# Cathode.net
KiCad netlist of a schematic drawn in Altium Designer
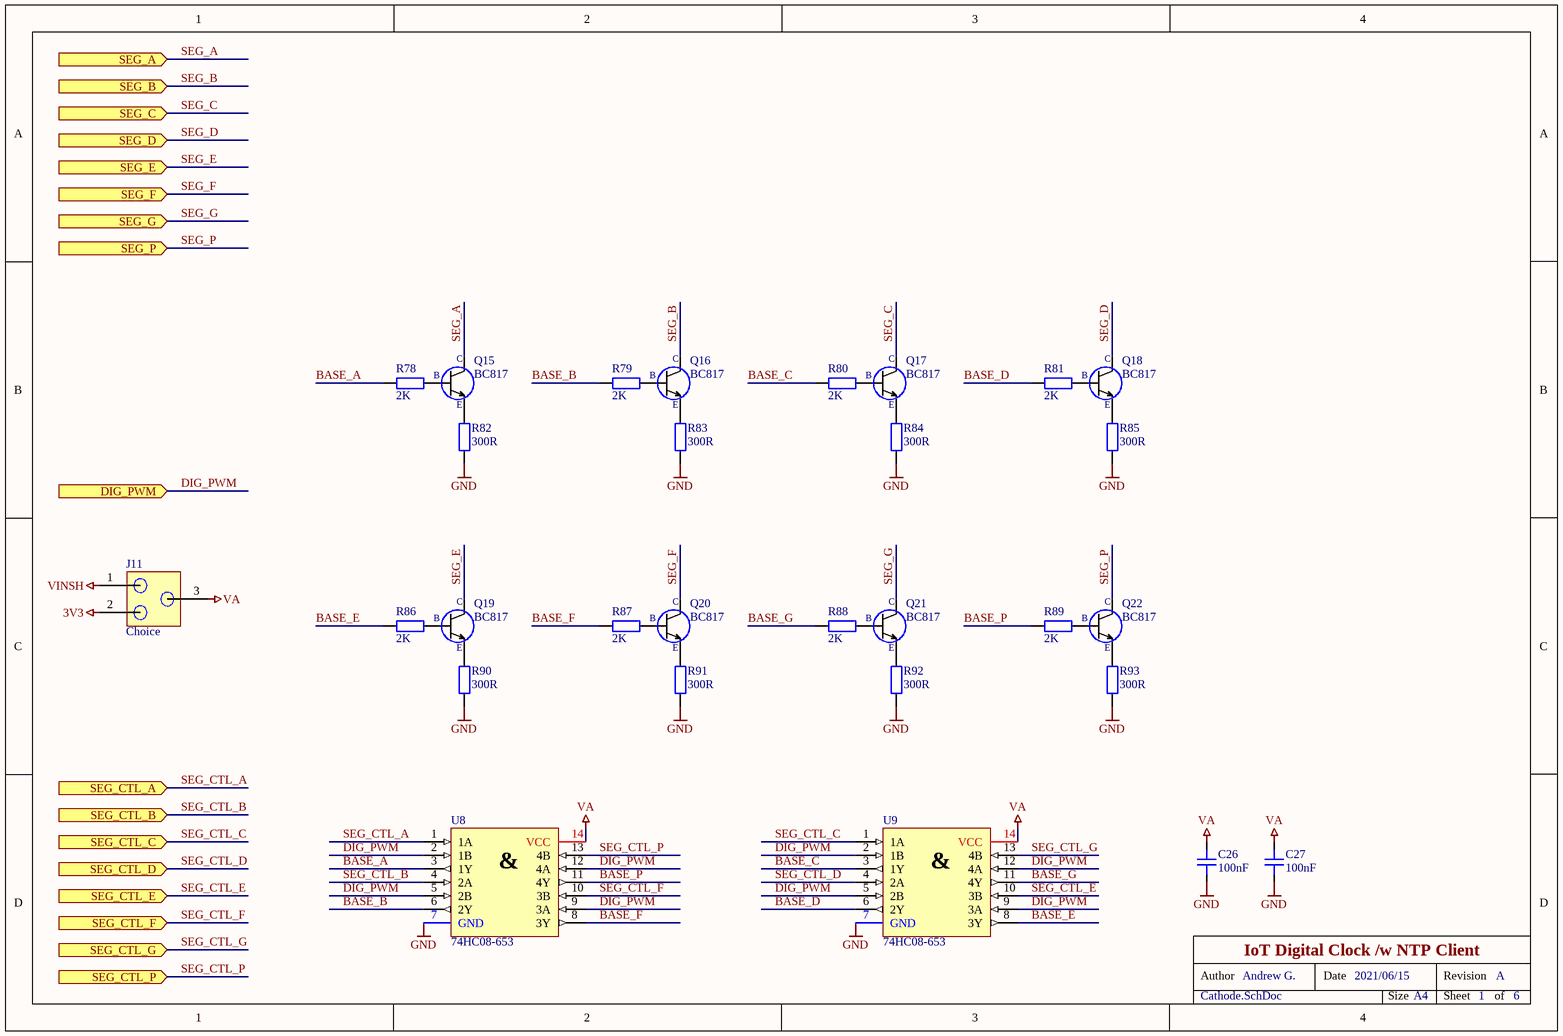
[diagram p0: Cathode.SchDoc]

(export (version "E")
  (design (tool "Eeschema 10.0.6"))
  (components
    (comp (ref "C26")
      (value "100nF")
      (footprint "0805C_RF_M")
      (description "Capacitor")
      (fields (field (name "TOLERANCE") "?") (field (name "MANUFACTURER") "Generic Brand"))
      (libsource (lib "AG.Generic") (part "C"))
    )
    (comp (ref "C27")
      (value "100nF")
      (footprint "0805C_RF_M")
      (description "Capacitor")
      (fields (field (name "TOLERANCE") "?") (field (name "MANUFACTURER") "Generic Brand"))
      (libsource (lib "AG.Generic") (part "C"))
    )
    (comp (ref "J11") (value "Choice") (footprint "CHOICE_R0805") (libsource (lib "AG.Misc") (part "Choice")))
    (comp (ref "Q15")
      (value "BC817")
      (footprint "IRLML_SOT-23")
      (description "TRANS NPN 45V 0.5A SOT23")
      (fields
        (field (name "MANUFACTURER") "Nexperia USA Inc.")
        (field (name "MANUFACTURER PART NO") "BC817-40,215")
      )
      (libsource (lib "AG.Discrete") (part "BC817-40-215"))
    )
    (comp (ref "Q16")
      (value "BC817")
      (footprint "IRLML_SOT-23")
      (description "TRANS NPN 45V 0.5A SOT23")
      (fields
        (field (name "MANUFACTURER") "Nexperia USA Inc.")
        (field (name "MANUFACTURER PART NO") "BC817-40,215")
      )
      (libsource (lib "AG.Discrete") (part "BC817-40-215"))
    )
    (comp (ref "Q17")
      (value "BC817")
      (footprint "IRLML_SOT-23")
      (description "TRANS NPN 45V 0.5A SOT23")
      (fields
        (field (name "MANUFACTURER") "Nexperia USA Inc.")
        (field (name "MANUFACTURER PART NO") "BC817-40,215")
      )
      (libsource (lib "AG.Discrete") (part "BC817-40-215"))
    )
    (comp (ref "Q18")
      (value "BC817")
      (footprint "IRLML_SOT-23")
      (description "TRANS NPN 45V 0.5A SOT23")
      (fields
        (field (name "MANUFACTURER") "Nexperia USA Inc.")
        (field (name "MANUFACTURER PART NO") "BC817-40,215")
      )
      (libsource (lib "AG.Discrete") (part "BC817-40-215"))
    )
    (comp (ref "Q19")
      (value "BC817")
      (footprint "IRLML_SOT-23")
      (description "TRANS NPN 45V 0.5A SOT23")
      (fields
        (field (name "MANUFACTURER") "Nexperia USA Inc.")
        (field (name "MANUFACTURER PART NO") "BC817-40,215")
      )
      (libsource (lib "AG.Discrete") (part "BC817-40-215"))
    )
    (comp (ref "Q20")
      (value "BC817")
      (footprint "IRLML_SOT-23")
      (description "TRANS NPN 45V 0.5A SOT23")
      (fields
        (field (name "MANUFACTURER") "Nexperia USA Inc.")
        (field (name "MANUFACTURER PART NO") "BC817-40,215")
      )
      (libsource (lib "AG.Discrete") (part "BC817-40-215"))
    )
    (comp (ref "Q21")
      (value "BC817")
      (footprint "IRLML_SOT-23")
      (description "TRANS NPN 45V 0.5A SOT23")
      (fields
        (field (name "MANUFACTURER") "Nexperia USA Inc.")
        (field (name "MANUFACTURER PART NO") "BC817-40,215")
      )
      (libsource (lib "AG.Discrete") (part "BC817-40-215"))
    )
    (comp (ref "Q22")
      (value "BC817")
      (footprint "IRLML_SOT-23")
      (description "TRANS NPN 45V 0.5A SOT23")
      (fields
        (field (name "MANUFACTURER") "Nexperia USA Inc.")
        (field (name "MANUFACTURER PART NO") "BC817-40,215")
      )
      (libsource (lib "AG.Discrete") (part "BC817-40-215"))
    )
    (comp (ref "R78")
      (value "2K")
      (footprint "0805R_RF_M")
      (description "Resistor")
      (fields (field (name "TOLERANCE") "?") (field (name "MANUFACTURER") "Generic Brand"))
      (libsource (lib "AG.Generic") (part "R"))
    )
    (comp (ref "R79")
      (value "2K")
      (footprint "0805R_RF_M")
      (description "Resistor")
      (fields (field (name "TOLERANCE") "?") (field (name "MANUFACTURER") "Generic Brand"))
      (libsource (lib "AG.Generic") (part "R"))
    )
    (comp (ref "R80")
      (value "2K")
      (footprint "0805R_RF_M")
      (description "Resistor")
      (fields (field (name "TOLERANCE") "?") (field (name "MANUFACTURER") "Generic Brand"))
      (libsource (lib "AG.Generic") (part "R"))
    )
    (comp (ref "R81")
      (value "2K")
      (footprint "0805R_RF_M")
      (description "Resistor")
      (fields (field (name "TOLERANCE") "?") (field (name "MANUFACTURER") "Generic Brand"))
      (libsource (lib "AG.Generic") (part "R"))
    )
    (comp (ref "R82")
      (value "300R")
      (footprint "0805R_RF_M")
      (description "Resistor")
      (fields (field (name "TOLERANCE") "?") (field (name "MANUFACTURER") "Generic Brand"))
      (libsource (lib "AG.Generic") (part "R"))
    )
    (comp (ref "R83")
      (value "300R")
      (footprint "0805R_RF_M")
      (description "Resistor")
      (fields (field (name "TOLERANCE") "?") (field (name "MANUFACTURER") "Generic Brand"))
      (libsource (lib "AG.Generic") (part "R"))
    )
    (comp (ref "R84")
      (value "300R")
      (footprint "0805R_RF_M")
      (description "Resistor")
      (fields (field (name "TOLERANCE") "?") (field (name "MANUFACTURER") "Generic Brand"))
      (libsource (lib "AG.Generic") (part "R"))
    )
    (comp (ref "R85")
      (value "300R")
      (footprint "0805R_RF_M")
      (description "Resistor")
      (fields (field (name "TOLERANCE") "?") (field (name "MANUFACTURER") "Generic Brand"))
      (libsource (lib "AG.Generic") (part "R"))
    )
    (comp (ref "R86")
      (value "2K")
      (footprint "0805R_RF_M")
      (description "Resistor")
      (fields (field (name "TOLERANCE") "?") (field (name "MANUFACTURER") "Generic Brand"))
      (libsource (lib "AG.Generic") (part "R"))
    )
    (comp (ref "R87")
      (value "2K")
      (footprint "0805R_RF_M")
      (description "Resistor")
      (fields (field (name "TOLERANCE") "?") (field (name "MANUFACTURER") "Generic Brand"))
      (libsource (lib "AG.Generic") (part "R"))
    )
    (comp (ref "R88")
      (value "2K")
      (footprint "0805R_RF_M")
      (description "Resistor")
      (fields (field (name "TOLERANCE") "?") (field (name "MANUFACTURER") "Generic Brand"))
      (libsource (lib "AG.Generic") (part "R"))
    )
    (comp (ref "R89")
      (value "2K")
      (footprint "0805R_RF_M")
      (description "Resistor")
      (fields (field (name "TOLERANCE") "?") (field (name "MANUFACTURER") "Generic Brand"))
      (libsource (lib "AG.Generic") (part "R"))
    )
    (comp (ref "R90")
      (value "300R")
      (footprint "0805R_RF_M")
      (description "Resistor")
      (fields (field (name "TOLERANCE") "?") (field (name "MANUFACTURER") "Generic Brand"))
      (libsource (lib "AG.Generic") (part "R"))
    )
    (comp (ref "R91")
      (value "300R")
      (footprint "0805R_RF_M")
      (description "Resistor")
      (fields (field (name "TOLERANCE") "?") (field (name "MANUFACTURER") "Generic Brand"))
      (libsource (lib "AG.Generic") (part "R"))
    )
    (comp (ref "R92")
      (value "300R")
      (footprint "0805R_RF_M")
      (description "Resistor")
      (fields (field (name "TOLERANCE") "?") (field (name "MANUFACTURER") "Generic Brand"))
      (libsource (lib "AG.Generic") (part "R"))
    )
    (comp (ref "R93")
      (value "300R")
      (footprint "0805R_RF_M")
      (description "Resistor")
      (fields (field (name "TOLERANCE") "?") (field (name "MANUFACTURER") "Generic Brand"))
      (libsource (lib "AG.Generic") (part "R"))
    )
    (comp (ref "U8")
      (value "74HC08-653")
      (footprint "SOIC-14")
      (fields (field (name "MANUFACTURER") "NXP"))
      (libsource (lib "AG.IC") (part "74HC08-653"))
    )
    (comp (ref "U9")
      (value "74HC08-653")
      (footprint "SOIC-14")
      (fields (field (name "MANUFACTURER") "NXP"))
      (libsource (lib "AG.IC") (part "74HC08-653"))
    )
  )
  (nets
    (net (code "1") (name "/BASE_A") (class "Default")
      (node (ref "R78") (pin "1") (pintype "passive"))
      (node (ref "U8") (pin "3") (pinfunction "1Y_3") (pintype "output"))
    )
    (net (code "2") (name "/BASE_B") (class "Default")
      (node (ref "R79") (pin "1") (pintype "passive"))
      (node (ref "U8") (pin "6") (pinfunction "2Y_6") (pintype "output"))
    )
    (net (code "3") (name "/BASE_C") (class "Default")
      (node (ref "R80") (pin "1") (pintype "passive"))
      (node (ref "U9") (pin "3") (pinfunction "1Y_3") (pintype "output"))
    )
    (net (code "4") (name "/BASE_D") (class "Default")
      (node (ref "R81") (pin "1") (pintype "passive"))
      (node (ref "U9") (pin "6") (pinfunction "2Y_6") (pintype "output"))
    )
    (net (code "5") (name "/BASE_E") (class "Default")
      (node (ref "R86") (pin "1") (pintype "passive"))
      (node (ref "U9") (pin "8") (pinfunction "3Y_8") (pintype "output"))
    )
    (net (code "6") (name "/BASE_F") (class "Default")
      (node (ref "R87") (pin "1") (pintype "passive"))
      (node (ref "U8") (pin "8") (pinfunction "3Y_8") (pintype "output"))
    )
    (net (code "7") (name "/BASE_G") (class "Default")
      (node (ref "R88") (pin "1") (pintype "passive"))
      (node (ref "U9") (pin "11") (pinfunction "4Y_11") (pintype "output"))
    )
    (net (code "8") (name "/BASE_P") (class "Default")
      (node (ref "R89") (pin "1") (pintype "passive"))
      (node (ref "U8") (pin "11") (pinfunction "4Y_11") (pintype "output"))
    )
    (net (code "9") (name "/DIG_PWM") (class "Default")
      (node (ref "U8") (pin "12") (pinfunction "4A_12") (pintype "input"))
      (node (ref "U8") (pin "2") (pinfunction "1B_2") (pintype "input"))
      (node (ref "U8") (pin "5") (pinfunction "2B_5") (pintype "input"))
      (node (ref "U8") (pin "9") (pinfunction "3A_9") (pintype "input"))
      (node (ref "U9") (pin "12") (pinfunction "4A_12") (pintype "input"))
      (node (ref "U9") (pin "2") (pinfunction "1B_2") (pintype "input"))
      (node (ref "U9") (pin "5") (pinfunction "2B_5") (pintype "input"))
      (node (ref "U9") (pin "9") (pinfunction "3A_9") (pintype "input"))
    )
    (net (code "10") (name "/SEG_A") (class "Default")
      (node (ref "Q15") (pin "3") (pinfunction "Collector_3") (pintype "passive"))
    )
    (net (code "11") (name "/SEG_B") (class "Default")
      (node (ref "Q16") (pin "3") (pinfunction "Collector_3") (pintype "passive"))
    )
    (net (code "12") (name "/SEG_C") (class "Default")
      (node (ref "Q17") (pin "3") (pinfunction "Collector_3") (pintype "passive"))
    )
    (net (code "13") (name "/SEG_CTL_A") (class "Default")
      (node (ref "U8") (pin "1") (pinfunction "1A_1") (pintype "input"))
    )
    (net (code "14") (name "/SEG_CTL_B") (class "Default")
      (node (ref "U8") (pin "4") (pinfunction "2A_4") (pintype "input"))
    )
    (net (code "15") (name "/SEG_CTL_C") (class "Default")
      (node (ref "U9") (pin "1") (pinfunction "1A_1") (pintype "input"))
    )
    (net (code "16") (name "/SEG_CTL_D") (class "Default")
      (node (ref "U9") (pin "4") (pinfunction "2A_4") (pintype "input"))
    )
    (net (code "17") (name "/SEG_CTL_E") (class "Default")
      (node (ref "U9") (pin "10") (pinfunction "3B_10") (pintype "input"))
    )
    (net (code "18") (name "/SEG_CTL_F") (class "Default")
      (node (ref "U8") (pin "10") (pinfunction "3B_10") (pintype "input"))
    )
    (net (code "19") (name "/SEG_CTL_G") (class "Default")
      (node (ref "U9") (pin "13") (pinfunction "4B_13") (pintype "input"))
    )
    (net (code "20") (name "/SEG_CTL_P") (class "Default")
      (node (ref "U8") (pin "13") (pinfunction "4B_13") (pintype "input"))
    )
    (net (code "21") (name "/SEG_D") (class "Default")
      (node (ref "Q18") (pin "3") (pinfunction "Collector_3") (pintype "passive"))
    )
    (net (code "22") (name "/SEG_E") (class "Default")
      (node (ref "Q19") (pin "3") (pinfunction "Collector_3") (pintype "passive"))
    )
    (net (code "23") (name "/SEG_F") (class "Default")
      (node (ref "Q20") (pin "3") (pinfunction "Collector_3") (pintype "passive"))
    )
    (net (code "24") (name "/SEG_G") (class "Default")
      (node (ref "Q21") (pin "3") (pinfunction "Collector_3") (pintype "passive"))
    )
    (net (code "25") (name "/SEG_P") (class "Default")
      (node (ref "Q22") (pin "3") (pinfunction "Collector_3") (pintype "passive"))
    )
    (net (code "26") (name "3V3") (class "Default")
      (node (ref "J11") (pin "2") (pinfunction "2_2") (pintype "passive"))
    )
    (net (code "27") (name "GND") (class "Default")
      (node (ref "C26") (pin "1") (pinfunction "1_1") (pintype "passive"))
      (node (ref "C27") (pin "1") (pinfunction "1_1") (pintype "passive"))
      (node (ref "R82") (pin "1") (pintype "passive"))
      (node (ref "R83") (pin "1") (pintype "passive"))
      (node (ref "R84") (pin "1") (pintype "passive"))
      (node (ref "R85") (pin "1") (pintype "passive"))
      (node (ref "R90") (pin "1") (pintype "passive"))
      (node (ref "R91") (pin "1") (pintype "passive"))
      (node (ref "R92") (pin "1") (pintype "passive"))
      (node (ref "R93") (pin "1") (pintype "passive"))
      (node (ref "U8") (pin "7") (pinfunction "GND_7") (pintype "power_in"))
      (node (ref "U9") (pin "7") (pinfunction "GND_7") (pintype "power_in"))
    )
    (net (code "28") (name "Net-(Q15-Base)") (class "Default")
      (node (ref "Q15") (pin "1") (pinfunction "Base_1") (pintype "passive"))
      (node (ref "R78") (pin "2") (pintype "passive"))
    )
    (net (code "29") (name "Net-(Q15-Emmiter)") (class "Default")
      (node (ref "Q15") (pin "2") (pinfunction "Emmiter_2") (pintype "passive"))
      (node (ref "R82") (pin "2") (pintype "passive"))
    )
    (net (code "30") (name "Net-(Q16-Base)") (class "Default")
      (node (ref "Q16") (pin "1") (pinfunction "Base_1") (pintype "passive"))
      (node (ref "R79") (pin "2") (pintype "passive"))
    )
    (net (code "31") (name "Net-(Q16-Emmiter)") (class "Default")
      (node (ref "Q16") (pin "2") (pinfunction "Emmiter_2") (pintype "passive"))
      (node (ref "R83") (pin "2") (pintype "passive"))
    )
    (net (code "32") (name "Net-(Q17-Base)") (class "Default")
      (node (ref "Q17") (pin "1") (pinfunction "Base_1") (pintype "passive"))
      (node (ref "R80") (pin "2") (pintype "passive"))
    )
    (net (code "33") (name "Net-(Q17-Emmiter)") (class "Default")
      (node (ref "Q17") (pin "2") (pinfunction "Emmiter_2") (pintype "passive"))
      (node (ref "R84") (pin "2") (pintype "passive"))
    )
    (net (code "34") (name "Net-(Q18-Base)") (class "Default")
      (node (ref "Q18") (pin "1") (pinfunction "Base_1") (pintype "passive"))
      (node (ref "R81") (pin "2") (pintype "passive"))
    )
    (net (code "35") (name "Net-(Q18-Emmiter)") (class "Default")
      (node (ref "Q18") (pin "2") (pinfunction "Emmiter_2") (pintype "passive"))
      (node (ref "R85") (pin "2") (pintype "passive"))
    )
    (net (code "36") (name "Net-(Q19-Base)") (class "Default")
      (node (ref "Q19") (pin "1") (pinfunction "Base_1") (pintype "passive"))
      (node (ref "R86") (pin "2") (pintype "passive"))
    )
    (net (code "37") (name "Net-(Q19-Emmiter)") (class "Default")
      (node (ref "Q19") (pin "2") (pinfunction "Emmiter_2") (pintype "passive"))
      (node (ref "R90") (pin "2") (pintype "passive"))
    )
    (net (code "38") (name "Net-(Q20-Base)") (class "Default")
      (node (ref "Q20") (pin "1") (pinfunction "Base_1") (pintype "passive"))
      (node (ref "R87") (pin "2") (pintype "passive"))
    )
    (net (code "39") (name "Net-(Q20-Emmiter)") (class "Default")
      (node (ref "Q20") (pin "2") (pinfunction "Emmiter_2") (pintype "passive"))
      (node (ref "R91") (pin "2") (pintype "passive"))
    )
    (net (code "40") (name "Net-(Q21-Base)") (class "Default")
      (node (ref "Q21") (pin "1") (pinfunction "Base_1") (pintype "passive"))
      (node (ref "R88") (pin "2") (pintype "passive"))
    )
    (net (code "41") (name "Net-(Q21-Emmiter)") (class "Default")
      (node (ref "Q21") (pin "2") (pinfunction "Emmiter_2") (pintype "passive"))
      (node (ref "R92") (pin "2") (pintype "passive"))
    )
    (net (code "42") (name "Net-(Q22-Base)") (class "Default")
      (node (ref "Q22") (pin "1") (pinfunction "Base_1") (pintype "passive"))
      (node (ref "R89") (pin "2") (pintype "passive"))
    )
    (net (code "43") (name "Net-(Q22-Emmiter)") (class "Default")
      (node (ref "Q22") (pin "2") (pinfunction "Emmiter_2") (pintype "passive"))
      (node (ref "R93") (pin "2") (pintype "passive"))
    )
    (net (code "44") (name "VA") (class "Default")
      (node (ref "C26") (pin "2") (pinfunction "2_2") (pintype "passive"))
      (node (ref "C27") (pin "2") (pinfunction "2_2") (pintype "passive"))
      (node (ref "J11") (pin "3") (pinfunction "3_3") (pintype "passive"))
      (node (ref "U8") (pin "14") (pinfunction "VCC_14") (pintype "power_in"))
      (node (ref "U9") (pin "14") (pinfunction "VCC_14") (pintype "power_in"))
    )
    (net (code "45") (name "VINSH") (class "Default")
      (node (ref "J11") (pin "1") (pinfunction "1_1") (pintype "passive"))
    )
  )
)
